# PWR_Buck_4V_20A.net
KiCad netlist of a schematic drawn in Altium Designer
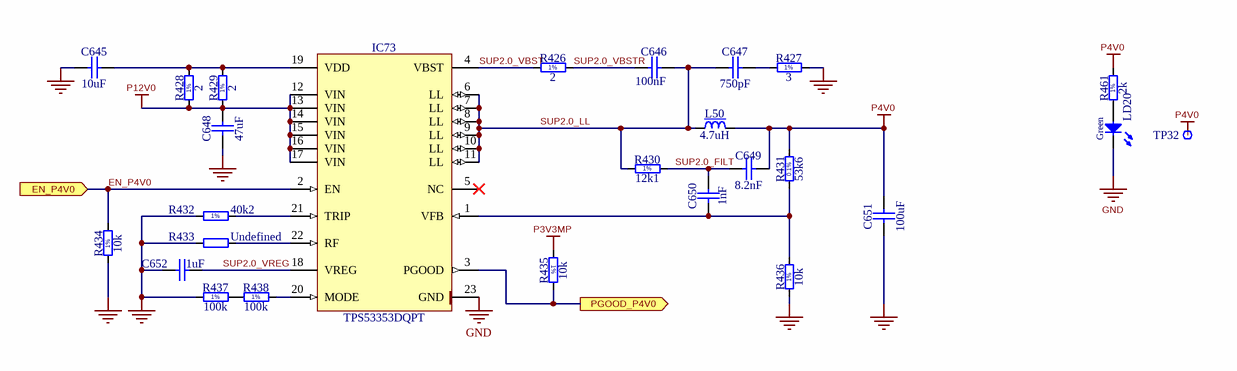
[diagram p0: PWR_Buck_4V_20A.SchDoc]

(export (version "E")
  (design (tool "Eeschema 10.0.6"))
  (components
    (comp (ref "C645")
      (value "10uF")
      (footprint "CAPC3216X180N")
      (description "Non-polarised capacitor")
      (fields
        (field (name "MANUFACTURER PART NUMBER") "CC1206_10uF_25V_10%_X7R")
        (field (name "MANUFACTURER") "GENERIC")
        (field (name "AUTHOR") "CERN DEM JLC")
      )
      (libsource (lib "Capacitors") (part "Capacitor - non polarized"))
    )
    (comp (ref "C646")
      (value "100nF")
      (footprint "CAPC1005X55N")
      (description "Non-polarised capacitor")
      (fields
        (field (name "MANUFACTURER PART NUMBER") "CC0402_100NF_16V_10%_X5R")
        (field (name "MANUFACTURER") "GENERIC")
        (field (name "AUTHOR") "CERN DEM JLC")
      )
      (libsource (lib "Capacitors") (part "Capacitor - non polarized"))
    )
    (comp (ref "C647")
      (value "750pF")
      (footprint "CAPC1608X87N")
      (description "Non-polarised capacitor")
      (fields
        (field (name "PART NUMBER") "CC0603_750PF_50V_5%_C0G")
        (field (name "VOLTAGE") "50V")
        (field (name "AUTHOR") "CERN DEM JLC")
      )
      (libsource (lib "Capacitors") (part "Capacitor - non polarized"))
    )
    (comp (ref "C648")
      (value "47uF")
      (footprint "CAPC3225X270N")
      (description "Non-polarised capacitor")
      (fields
        (field (name "PART NUMBER") "CC1210_47UF_16V_20%_X5R")
        (field (name "VOLTAGE") "16V")
        (field (name "AUTHOR") "CERN DEM MR")
      )
      (libsource (lib "Capacitors") (part "Capacitor - non polarized"))
    )
    (comp (ref "C649")
      (value "8.2nF")
      (footprint "CAPC1608X87N")
      (description "Non-polarised capacitor")
      (fields
        (field (name "PART NUMBER") "CC0603_8.2NF_50V_5%_X7R")
        (field (name "VOLTAGE") "50V")
        (field (name "AUTHOR") "CERN DEM JLC")
      )
      (libsource (lib "Capacitors") (part "Capacitor - non polarized"))
    )
    (comp (ref "C650")
      (value "1nF")
      (footprint "CAPC1005X55N")
      (description "Non-polarised capacitor")
      (fields
        (field (name "MANUFACTURER PART NUMBER") "CC0402_1NF_50V_10%_X7R")
        (field (name "MANUFACTURER") "GENERIC")
        (field (name "AUTHOR") "CERN DEM JLC")
      )
      (libsource (lib "Capacitors") (part "Capacitor - non polarized"))
    )
    (comp (ref "C651")
      (value "100uF")
      (footprint "CAPC3216X180N")
      (description "Non-polarised capacitor")
      (fields
        (field (name "MANUFACTURER PART NUMBER") "CC1206_100UF_6.3V_20%_X5R")
        (field (name "MANUFACTURER") "GENERIC")
        (field (name "AUTHOR") "CERN DEM JLC")
      )
      (libsource (lib "Capacitors") (part "Capacitor - non polarized"))
    )
    (comp (ref "C652")
      (value "1uF")
      (footprint "CAPC1608X87N")
      (description "Non-polarised capacitor")
      (fields
        (field (name "MANUFACTURER PART NUMBER") "CC0603_1UF_25V_10%_X7R")
        (field (name "MANUFACTURER") "GENERIC")
        (field (name "AUTHOR") "CERN DEM JLC")
      )
      (libsource (lib "Capacitors") (part "Capacitor - non polarized"))
    )
    (comp (ref "IC73")
      (value "TPS53353DQPT")
      (footprint "SON50P500X600X150-23N-R334X557")
      (description "1.5V to 15V Input (4.5V to 25V Bias), 20A Synchronous Buck SWIFT™ Converter with Eco-mode™")
      (fields (field (name "MANUFACTURER") "TEXAS INSTRUMENTS"))
      (libsource (lib "TP_LIB") (part "TPS53353DQPT"))
    )
    (comp (ref "L50")
      (value "4.7uH")
      (footprint "IND_TDK_SPM6530")
      (description "Inductor With Core")
      (fields (field (name "PART NUMBER") "IND_4.7UH_20%_TDK_SPM6530") (field (name "POWER") "5.6A"))
      (libsource (lib "TP_LIB") (part "SPM6530T-4R7M"))
    )
    (comp (ref "LD20")
      (value "Green")
      (footprint "LED_OSRAM_LGL29K")
      (description "LED Green 1C 2A")
      (fields
        (field (name "MANUFACTURER PART NUMBER") "LG L29K-G2J1-24-Z")
        (field (name "MANUFACTURER") "OSRAM")
        (field (name "AUTHOR") "CERN DEM JLC")
      )
      (libsource (lib "ICs And Semiconductors") (part "LED Green 1C 2A"))
    )
    (comp (ref "R426")
      (value "2")
      (footprint "RESC1608X55N")
      (description "Resistor - 1%")
      (fields
        (field (name "MANUFACTURER PART NUMBER") "R0603_2R_1%_0.1W_200PPM")
        (field (name "MANUFACTURER") "GENERIC")
        (field (name "AUTHOR") "CERN DEM JLC")
      )
      (libsource (lib "Resistors") (part "Resistor - 1%"))
    )
    (comp (ref "R427")
      (value "3")
      (footprint "RESC3216X65N")
      (description "Resistor - 1%")
      (fields
        (field (name "MANUFACTURER PART NUMBER") "R1206_3R_1%_0.25W_200PPM")
        (field (name "MANUFACTURER") "GENERIC")
        (field (name "AUTHOR") "CERN DEM JLC")
      )
      (libsource (lib "Resistors") (part "Resistor - 1%"))
    )
    (comp (ref "R428")
      (value "2")
      (footprint "RESC1608X55N")
      (description "Resistor - 1%")
      (fields
        (field (name "MANUFACTURER PART NUMBER") "R0603_2R_1%_0.1W_200PPM")
        (field (name "MANUFACTURER") "GENERIC")
        (field (name "AUTHOR") "CERN DEM JLC")
      )
      (libsource (lib "Resistors") (part "Resistor - 1%"))
    )
    (comp (ref "R429")
      (value "2")
      (footprint "RESC1608X55N")
      (description "Resistor - 1%")
      (fields
        (field (name "MANUFACTURER PART NUMBER") "R0603_2R_1%_0.1W_200PPM")
        (field (name "MANUFACTURER") "GENERIC")
        (field (name "AUTHOR") "CERN DEM JLC")
      )
      (libsource (lib "Resistors") (part "Resistor - 1%"))
    )
    (comp (ref "R430")
      (value "12k1")
      (footprint "RESC1005X40N")
      (description "Resistor - 1%")
      (fields
        (field (name "PART NUMBER") "R0402_12K1_1%_0.0625W_100PPM")
        (field (name "POWER") "0.0625W")
        (field (name "AUTHOR") "CERN DEM JLC")
      )
      (libsource (lib "Resistors") (part "Resistor - 1%"))
    )
    (comp (ref "R431")
      (value "53k6")
      (footprint "RESC1608X55N")
      (description "Resistor - 0.1%")
      (fields
        (field (name "PART NUMBER") "R0603_53K6_0.1%_0.063W_10PPM")
        (field (name "POWER") "0.063W")
        (field (name "AUTHOR") "CERN DEM JLC")
      )
      (libsource (lib "Resistors") (part "Resistor - 0.1%"))
    )
    (comp (ref "R432")
      (value "40k2")
      (footprint "RESC2012X60N")
      (description "Resistor - 1%")
      (fields
        (field (name "PART NUMBER") "R0805_40K2_1%_0.125W_100PPM")
        (field (name "POWER") "0.125W")
        (field (name "AUTHOR") "CERN DEM JLC")
      )
      (libsource (lib "Resistors") (part "Resistor - 1%"))
    )
    (comp (ref "R433")
      (value "Undefined")
      (footprint "RESC1005X40N")
      (description "Resistor")
      (fields
        (field (name "MANUFACTURER PART NUMBER") "R0402_NO-VALUE")
        (field (name "AUTHOR") "CERN DEM JLC")
      )
      (libsource (lib "Resistors") (part "Resistor"))
    )
    (comp (ref "R434")
      (value "10k")
      (footprint "RESC1005X40N")
      (description "Resistor - 1%")
      (fields
        (field (name "MANUFACTURER PART NUMBER") "R0402_10K_1%_0.0625W_100PPM")
        (field (name "MANUFACTURER") "GENERIC")
        (field (name "AUTHOR") "CERN DEM JLC")
      )
      (libsource (lib "Resistors") (part "Resistor - 1%"))
    )
    (comp (ref "R435")
      (value "10k")
      (footprint "RESC1005X40N")
      (description "Resistor - 1%")
      (fields
        (field (name "MANUFACTURER PART NUMBER") "R0402_10K_1%_0.0625W_100PPM")
        (field (name "MANUFACTURER") "GENERIC")
        (field (name "AUTHOR") "CERN DEM JLC")
      )
      (libsource (lib "Resistors") (part "Resistor - 1%"))
    )
    (comp (ref "R436")
      (value "10k")
      (footprint "RESC1005X40N")
      (description "Resistor - 1%")
      (fields
        (field (name "PART NUMBER") "R0402_10K_1%_0.0625W_100PPM")
        (field (name "POWER") "0.0625W")
        (field (name "AUTHOR") "CERN DEM JLC")
      )
      (libsource (lib "Resistors") (part "Resistor - 1%"))
    )
    (comp (ref "R437")
      (value "100k")
      (footprint "RESC1005X40N")
      (description "Resistor - 1%")
      (fields
        (field (name "MANUFACTURER PART NUMBER") "R0402_100K_1%_0.0625W_100PPM")
        (field (name "MANUFACTURER") "GENERIC")
        (field (name "AUTHOR") "CERN DEM JLC")
      )
      (libsource (lib "Resistors") (part "Resistor - 1%"))
    )
    (comp (ref "R438")
      (value "100k")
      (footprint "RESC1005X40N")
      (description "Resistor - 1%")
      (fields
        (field (name "MANUFACTURER PART NUMBER") "R0402_100K_1%_0.0625W_100PPM")
        (field (name "MANUFACTURER") "GENERIC")
        (field (name "AUTHOR") "CERN DEM JLC")
      )
      (libsource (lib "Resistors") (part "Resistor - 1%"))
    )
    (comp (ref "R461")
      (value "2k")
      (footprint "RESC1005X40N")
      (description "Resistor - 1%")
      (fields
        (field (name "PART NUMBER") "R0402_2K_1%_0.0625W_100PPM")
        (field (name "POWER") "0.0625W")
        (field (name "AUTHOR") "CERN DEM JLC")
      )
      (libsource (lib "Resistors") (part "Resistor - 1%"))
    )
    (comp (ref "TP32")
      (value "Test Point")
      (footprint "TPS127")
      (fields (field (name "PART NUMBER") "SMD_PAD_1.27X1.27MM") (field (name "AUTHOR") "CERN DEM JLC"))
      (libsource (lib "Eletro-mechanical") (part "Test Point"))
    )
  )
  (nets
    (net (code "1") (name "/EN_P4V0") (class "Default")
      (node (ref "IC73") (pin "2") (pinfunction "EN_2") (pintype "input"))
      (node (ref "R434") (pin "1") (pinfunction "1_1") (pintype "passive"))
    )
    (net (code "2") (name "/PGOOD_P4V0") (class "Default")
      (node (ref "IC73") (pin "3") (pinfunction "PGOOD_3") (pintype "output"))
      (node (ref "R435") (pin "1") (pinfunction "1_1") (pintype "passive"))
    )
    (net (code "3") (name "/SUP2.0_FILT") (class "Default")
      (node (ref "C649") (pin "1") (pinfunction "1_1") (pintype "passive"))
      (node (ref "C650") (pin "2") (pinfunction "2_2") (pintype "passive"))
      (node (ref "R430") (pin "2") (pinfunction "2_2") (pintype "passive"))
    )
    (net (code "4") (name "/SUP2.0_LL") (class "Default")
      (node (ref "C646") (pin "2") (pinfunction "2_2") (pintype "passive"))
      (node (ref "C647") (pin "1") (pinfunction "1_1") (pintype "passive"))
      (node (ref "IC73") (pin "10") (pinfunction "LL_10") (pintype "bidirectional"))
      (node (ref "IC73") (pin "11") (pinfunction "LL_11") (pintype "bidirectional"))
      (node (ref "IC73") (pin "6") (pinfunction "LL_6") (pintype "bidirectional"))
      (node (ref "IC73") (pin "7") (pinfunction "LL_7") (pintype "bidirectional"))
      (node (ref "IC73") (pin "8") (pinfunction "LL_8") (pintype "bidirectional"))
      (node (ref "IC73") (pin "9") (pinfunction "LL_9") (pintype "bidirectional"))
      (node (ref "L50") (pin "1") (pinfunction "1_1") (pintype "passive"))
      (node (ref "R430") (pin "1") (pinfunction "1_1") (pintype "passive"))
    )
    (net (code "5") (name "/SUP2.0_VBST") (class "Default")
      (node (ref "IC73") (pin "4") (pinfunction "VBST_4") (pintype "power_in"))
      (node (ref "R426") (pin "1") (pinfunction "1_1") (pintype "passive"))
    )
    (net (code "6") (name "/SUP2.0_VBSTR") (class "Default")
      (node (ref "C646") (pin "1") (pinfunction "1_1") (pintype "passive"))
      (node (ref "R426") (pin "2") (pinfunction "2_2") (pintype "passive"))
    )
    (net (code "7") (name "/SUP2.0_VREG") (class "Default")
      (node (ref "C652") (pin "1") (pinfunction "1_1") (pintype "passive"))
      (node (ref "IC73") (pin "18") (pinfunction "VREG_18") (pintype "power_in"))
    )
    (net (code "8") (name "GND") (class "Default")
      (node (ref "C645") (pin "2") (pinfunction "2_2") (pintype "passive"))
      (node (ref "C648") (pin "1") (pinfunction "1_1") (pintype "passive"))
      (node (ref "C651") (pin "1") (pinfunction "1_1") (pintype "passive"))
      (node (ref "C652") (pin "2") (pinfunction "2_2") (pintype "passive"))
      (node (ref "IC73") (pin "23") (pinfunction "GND_23") (pintype "power_in"))
      (node (ref "LD20") (pin "1") (pinfunction "C_1") (pintype "passive"))
      (node (ref "R427") (pin "2") (pinfunction "2_2") (pintype "passive"))
      (node (ref "R432") (pin "2") (pinfunction "2_2") (pintype "passive"))
      (node (ref "R433") (pin "2") (pinfunction "2_2") (pintype "passive"))
      (node (ref "R434") (pin "2") (pinfunction "2_2") (pintype "passive"))
      (node (ref "R436") (pin "1") (pinfunction "1_1") (pintype "passive"))
      (node (ref "R437") (pin "1") (pinfunction "1_1") (pintype "passive"))
    )
    (net (code "9") (name "Net-(C647-Pad2)") (class "Default")
      (node (ref "C647") (pin "2") (pinfunction "2_2") (pintype "passive"))
      (node (ref "R427") (pin "1") (pinfunction "1_1") (pintype "passive"))
    )
    (net (code "10") (name "Net-(IC73-MODE)") (class "Default")
      (node (ref "IC73") (pin "20") (pinfunction "MODE_20") (pintype "input"))
      (node (ref "R438") (pin "2") (pinfunction "2_2") (pintype "passive"))
    )
    (net (code "11") (name "Net-(IC73-RF)") (class "Default")
      (node (ref "IC73") (pin "22") (pinfunction "RF_22") (pintype "input"))
      (node (ref "R433") (pin "1") (pinfunction "1_1") (pintype "passive"))
    )
    (net (code "12") (name "Net-(IC73-TRIP)") (class "Default")
      (node (ref "IC73") (pin "21") (pinfunction "TRIP_21") (pintype "input"))
      (node (ref "R432") (pin "1") (pinfunction "1_1") (pintype "passive"))
    )
    (net (code "13") (name "Net-(IC73-VDD)") (class "Default")
      (node (ref "C645") (pin "1") (pinfunction "1_1") (pintype "passive"))
      (node (ref "IC73") (pin "19") (pinfunction "VDD_19") (pintype "power_in"))
      (node (ref "R428") (pin "2") (pinfunction "2_2") (pintype "passive"))
      (node (ref "R429") (pin "2") (pinfunction "2_2") (pintype "passive"))
    )
    (net (code "14") (name "Net-(IC73-VFB)") (class "Default")
      (node (ref "C650") (pin "1") (pinfunction "1_1") (pintype "passive"))
      (node (ref "IC73") (pin "1") (pinfunction "VFB_1") (pintype "input"))
      (node (ref "R431") (pin "1") (pinfunction "1_1") (pintype "passive"))
      (node (ref "R436") (pin "2") (pinfunction "2_2") (pintype "passive"))
    )
    (net (code "15") (name "Net-(LD20-A)") (class "Default")
      (node (ref "LD20") (pin "2") (pinfunction "A_2") (pintype "passive"))
      (node (ref "R461") (pin "1") (pinfunction "1_1") (pintype "passive"))
    )
    (net (code "16") (name "Net-(R437-Pad2)") (class "Default")
      (node (ref "R437") (pin "2") (pinfunction "2_2") (pintype "passive"))
      (node (ref "R438") (pin "1") (pinfunction "1_1") (pintype "passive"))
    )
    (net (code "17") (name "P3V3MP") (class "Default")
      (node (ref "R435") (pin "2") (pinfunction "2_2") (pintype "passive"))
    )
    (net (code "18") (name "P4V0") (class "Default")
      (node (ref "C649") (pin "2") (pinfunction "2_2") (pintype "passive"))
      (node (ref "C651") (pin "2") (pinfunction "2_2") (pintype "passive"))
      (node (ref "L50") (pin "2") (pinfunction "2_2") (pintype "passive"))
      (node (ref "R431") (pin "2") (pinfunction "2_2") (pintype "passive"))
      (node (ref "R461") (pin "2") (pinfunction "2_2") (pintype "passive"))
      (node (ref "TP32") (pin "1") (pinfunction "1_1") (pintype "bidirectional"))
    )
    (net (code "19") (name "P12V0") (class "Default")
      (node (ref "C648") (pin "2") (pinfunction "2_2") (pintype "passive"))
      (node (ref "IC73") (pin "12") (pinfunction "VIN_12") (pintype "power_in"))
      (node (ref "IC73") (pin "13") (pinfunction "VIN_13") (pintype "power_in"))
      (node (ref "IC73") (pin "14") (pinfunction "VIN_14") (pintype "power_in"))
      (node (ref "IC73") (pin "15") (pinfunction "VIN_15") (pintype "power_in"))
      (node (ref "IC73") (pin "16") (pinfunction "VIN_16") (pintype "power_in"))
      (node (ref "IC73") (pin "17") (pinfunction "VIN_17") (pintype "power_in"))
      (node (ref "R428") (pin "1") (pinfunction "1_1") (pintype "passive"))
      (node (ref "R429") (pin "1") (pinfunction "1_1") (pintype "passive"))
    )
    (net (code "20") (name "unconnected-(IC73-NC-Pad5)") (class "Default")
      (node (ref "IC73") (pin "5") (pinfunction "NC_5") (pintype "passive+no_connect"))
    )
  )
)
